# 17_-_MECH.net
KiCad netlist of a schematic drawn in Altium Designer
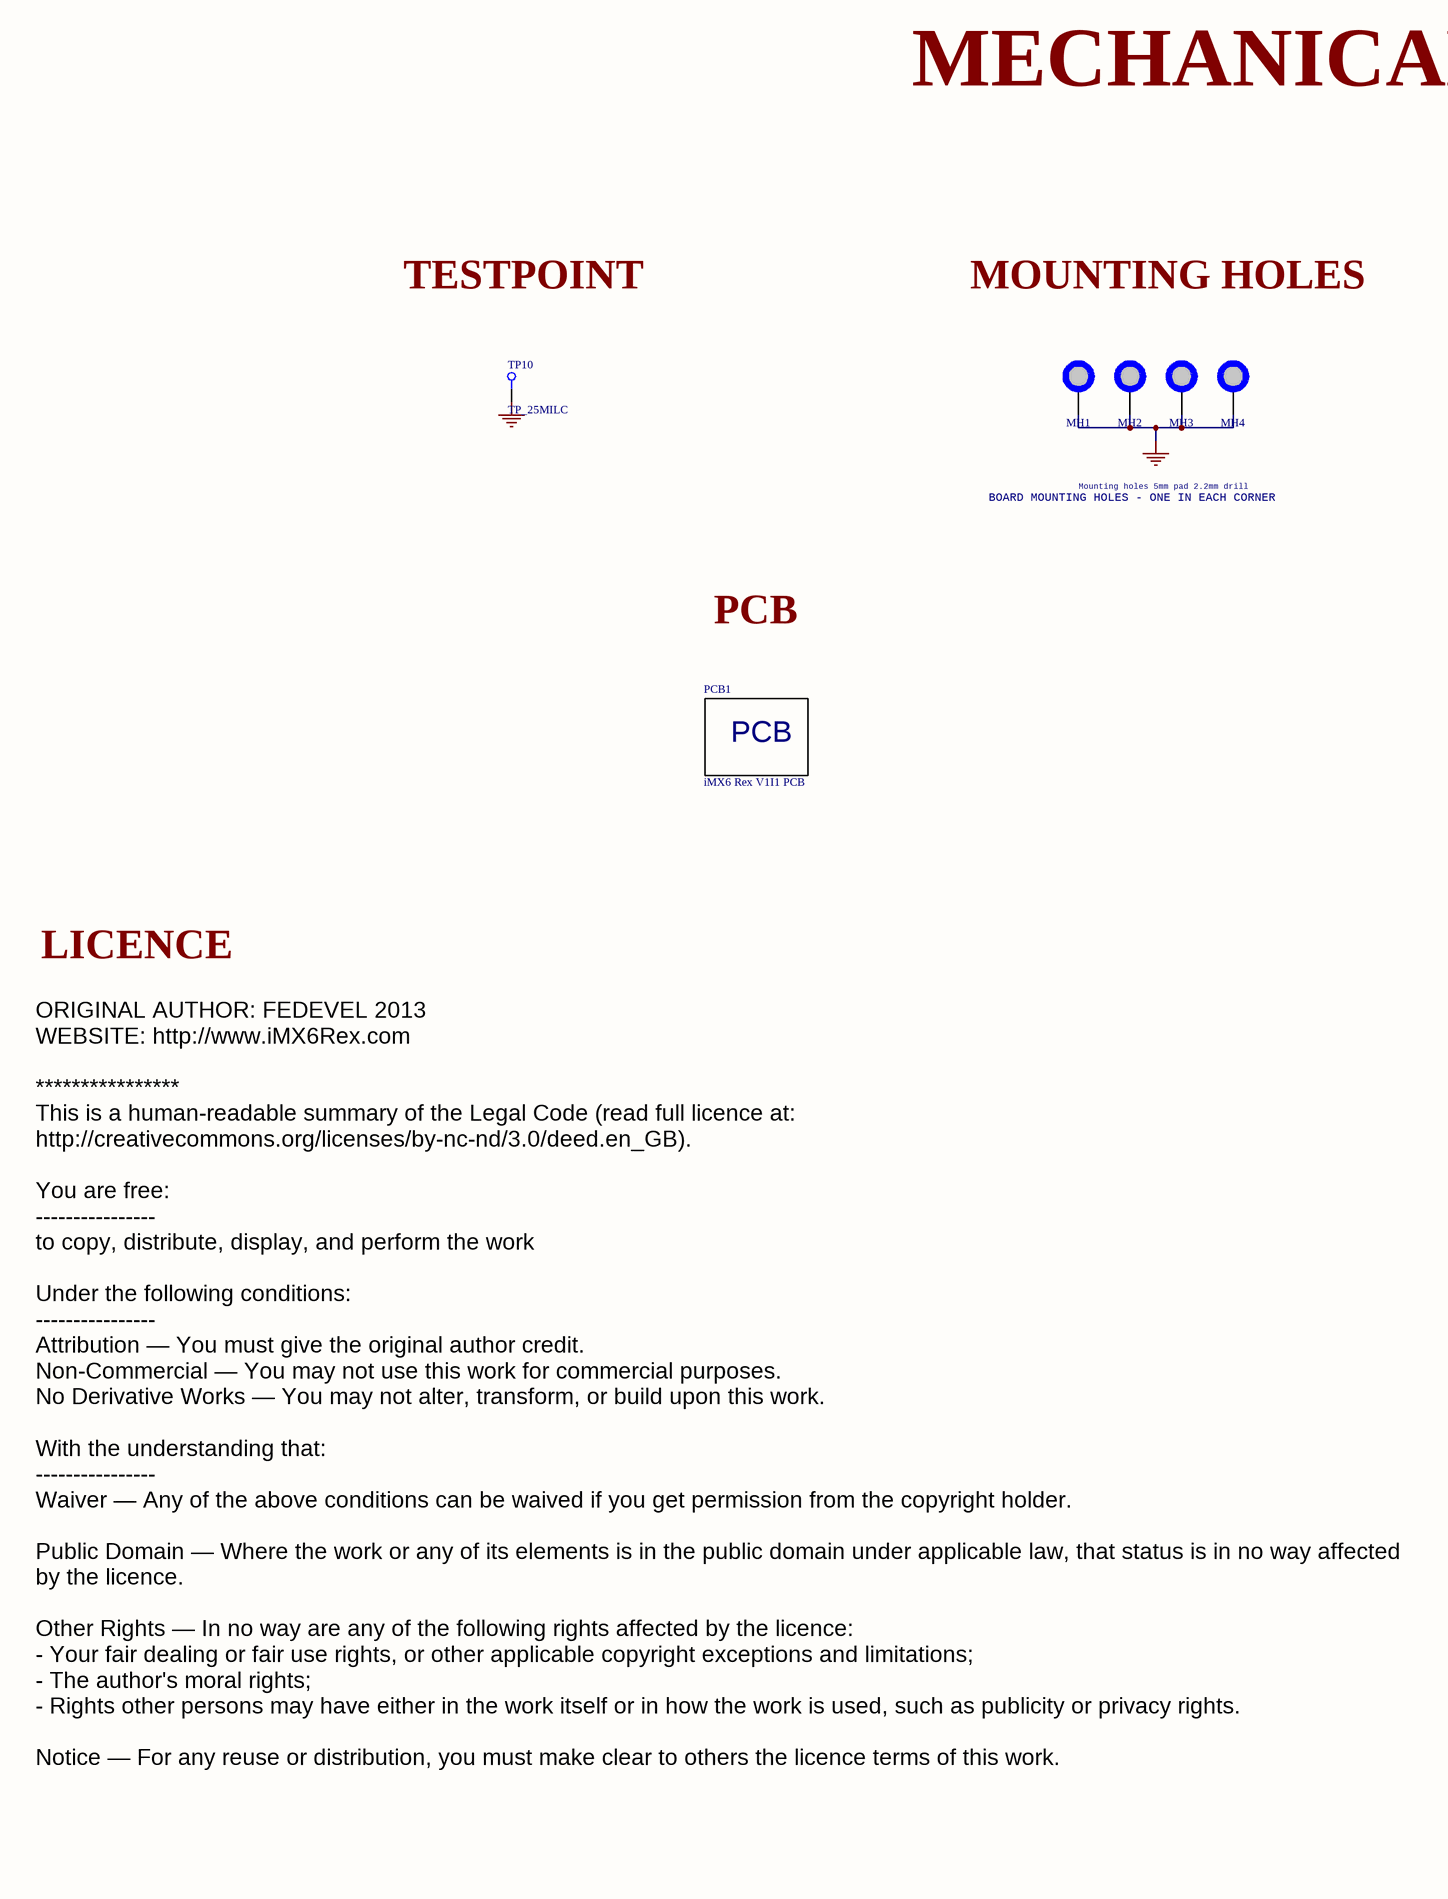
[diagram p0: [17] - MECH.SchDoc, left]
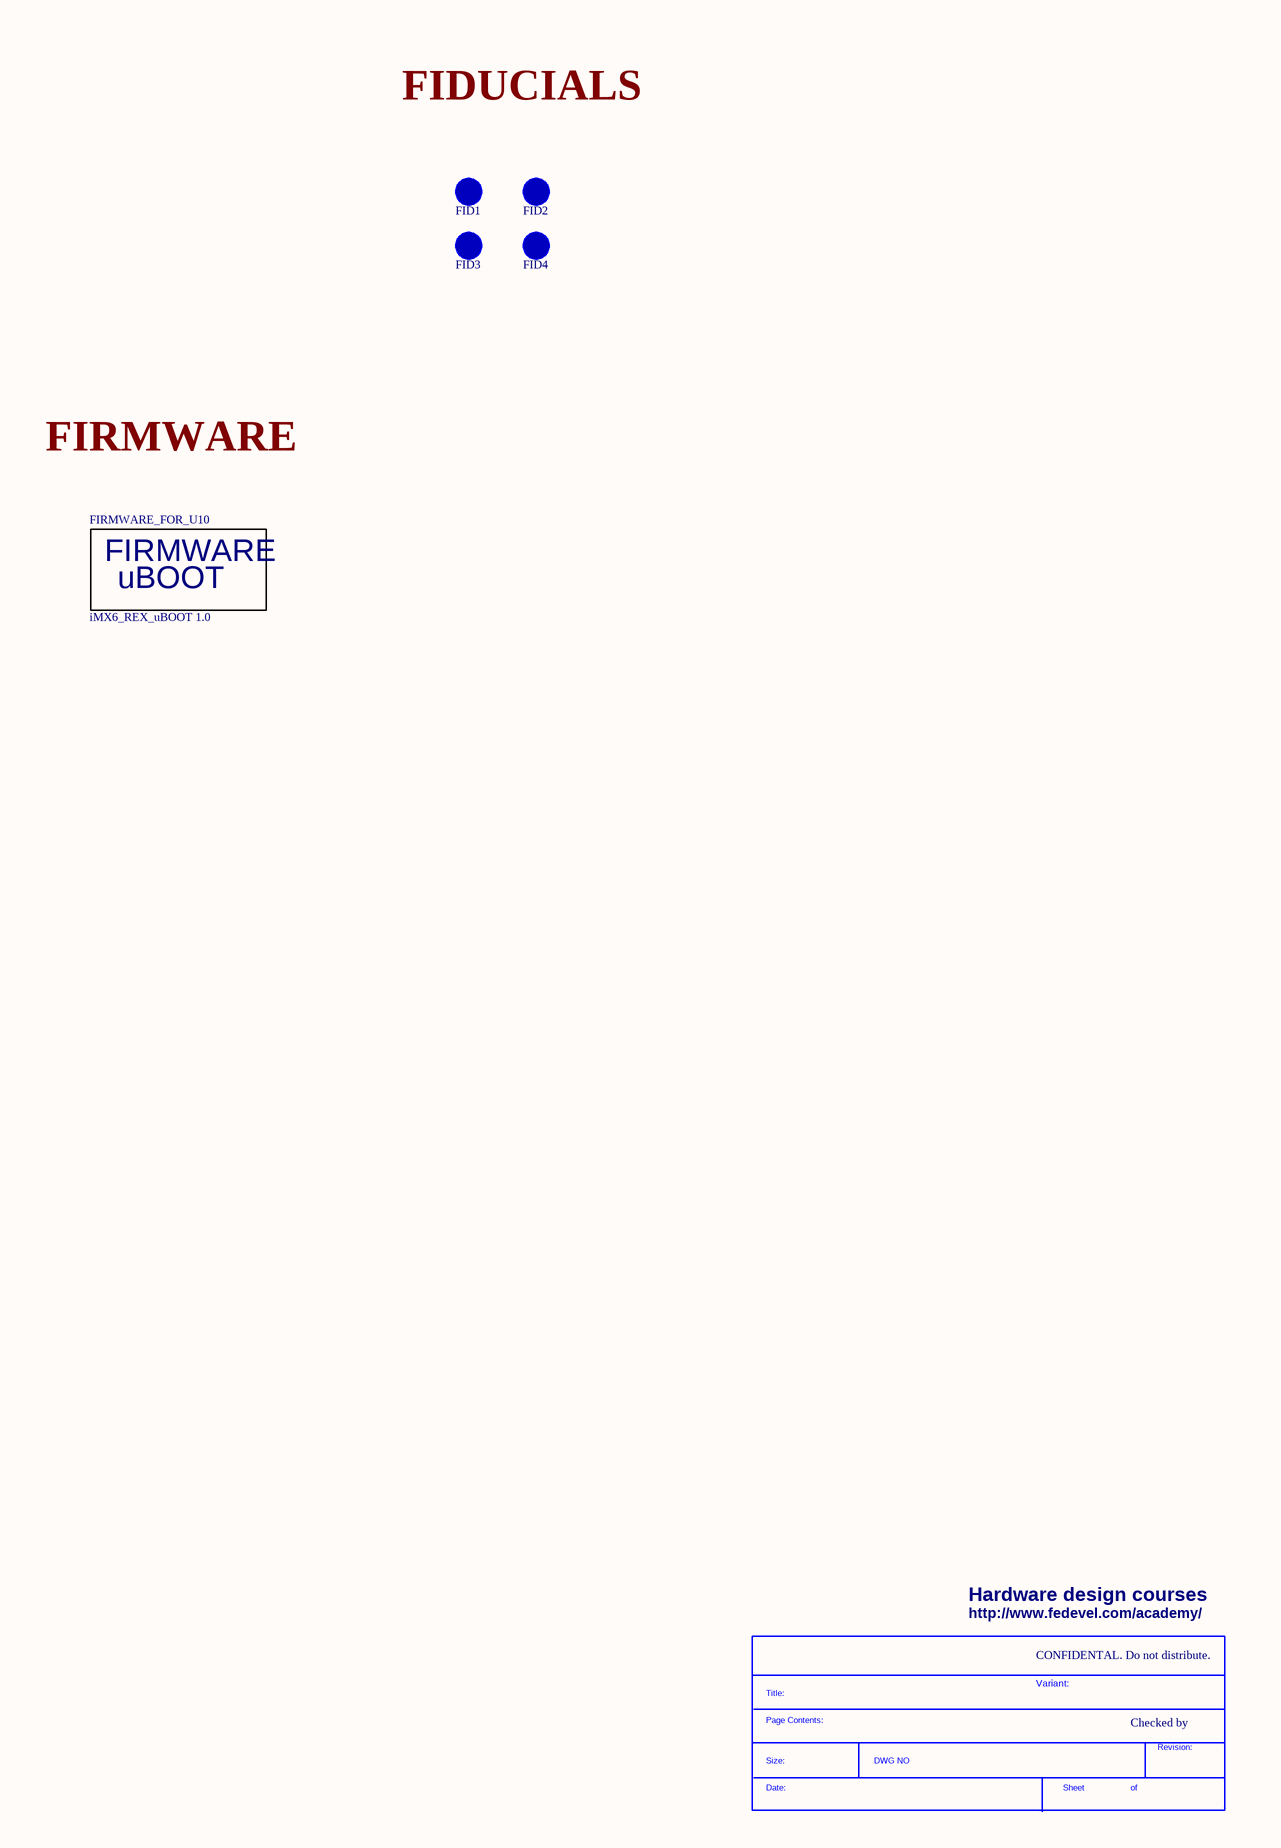
[diagram p1: [17] - MECH.SchDoc, right]

(export (version "E")
  (design (tool "Eeschema 10.0.6"))
  (components
    (comp (ref "FID1")
      (value "FID_1MM_SMALL")
      (footprint "FID_40X52D")
      (description "Fiducial 40mil Diameter, 52mil Mask")
      (libsource (lib "iMX6 Rex_V1I1") (part "FID_1MM_SMALL"))
    )
    (comp (ref "FID2")
      (value "FID_1MM_SMALL")
      (footprint "FID_40X52D")
      (description "Fiducial 40mil Diameter, 52mil Mask")
      (libsource (lib "iMX6 Rex_V1I1") (part "FID_1MM_SMALL"))
    )
    (comp (ref "FID3")
      (value "FID_1MM_SMALL")
      (footprint "FID_40X52D")
      (description "Fiducial 40mil Diameter, 52mil Mask")
      (libsource (lib "iMX6 Rex_V1I1") (part "FID_1MM_SMALL"))
    )
    (comp (ref "FID4")
      (value "FID_1MM_SMALL")
      (footprint "FID_40X52D")
      (description "Fiducial 40mil Diameter, 52mil Mask")
      (libsource (lib "iMX6 Rex_V1I1") (part "FID_1MM_SMALL"))
    )
    (comp (ref "FIRMWARE_FOR_U10")
      (value "iMX6_REX_uBOOT 1.0")
      (fields (field (name ".CREATOR") "MM"))
      (libsource (lib "iMX6 Rex_V1I1") (part "FIRMWARE_iMX6_Rex_uBOOT 1.0"))
    )
    (comp (ref "MH1")
      (value "MH_5MMC_2.2MMD")
      (footprint "MH_5MMD_2.2MMD")
      (description "Mounting Hole 5mm Diameter, 2.2mm Drill")
      (libsource (lib "iMX6 Rex_V1I1") (part "MH_5MMC_2.2MMD"))
    )
    (comp (ref "MH2")
      (value "MH_5MMC_2.2MMD")
      (footprint "MH_5MMD_2.2MMD")
      (description "Mounting Hole 5mm Diameter, 2.2mm Drill")
      (libsource (lib "iMX6 Rex_V1I1") (part "MH_5MMC_2.2MMD"))
    )
    (comp (ref "MH3")
      (value "MH_5MMC_2.2MMD")
      (footprint "MH_5MMD_2.2MMD")
      (description "Mounting Hole 5mm Diameter, 2.2mm Drill")
      (libsource (lib "iMX6 Rex_V1I1") (part "MH_5MMC_2.2MMD"))
    )
    (comp (ref "MH4")
      (value "MH_5MMC_2.2MMD")
      (footprint "MH_5MMD_2.2MMD")
      (description "Mounting Hole 5mm Diameter, 2.2mm Drill")
      (libsource (lib "iMX6 Rex_V1I1") (part "MH_5MMC_2.2MMD"))
    )
    (comp (ref "PCB1")
      (value "iMX6 Rex V1I1 PCB")
      (description "Printed Circuit Board")
      (fields (field (name ".CREATOR") "MM"))
      (libsource (lib "iMX6 Rex_V1I1") (part "PCB_iMX6_REX_V1I1"))
    )
    (comp (ref "TP10")
      (value "TP_25MILC")
      (footprint "TP_25C")
      (description "Test Point 25mil")
      (libsource (lib "iMX6 Rex_V1I1") (part "TP_25MILC"))
    )
  )
  (nets
    (net (code "1") (name "GND") (class "Default")
      (node (ref "MH1") (pin "1") (pinfunction "1_1") (pintype "passive"))
      (node (ref "MH2") (pin "1") (pinfunction "1_1") (pintype "passive"))
      (node (ref "MH3") (pin "1") (pinfunction "1_1") (pintype "passive"))
      (node (ref "MH4") (pin "1") (pinfunction "1_1") (pintype "passive"))
      (node (ref "TP10") (pin "1") (pinfunction "1_1") (pintype "passive"))
    )
  )
)
